# nRF51822_Module_Adapter.net
KiCad netlist of a schematic drawn in EAGLE
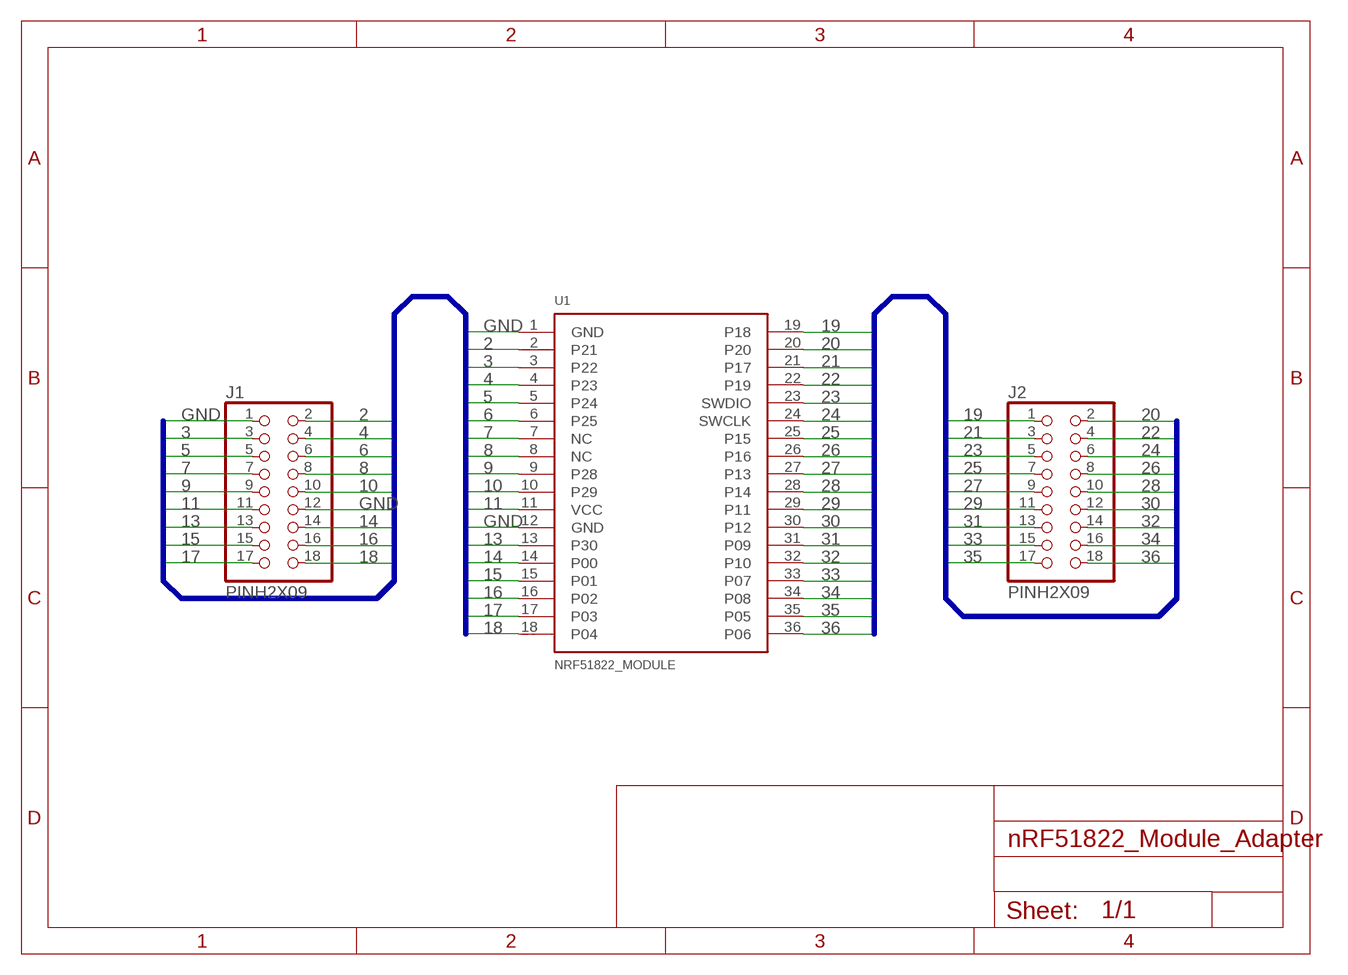
[diagram p0: schematic, sheet 1]

(export (version "E")
  (design (tool "Eeschema 10.0.6"))
  (components
    (comp (ref "J1")
      (value "PINH2X09")
      (footprint "eagle-import:PINH2X09")
      (libsource (lib "eagle-import") (part "PINH2X09"))
    )
    (comp (ref "J2")
      (value "PINH2X09")
      (footprint "eagle-import:PINH2X09")
      (libsource (lib "eagle-import") (part "PINH2X09"))
    )
    (comp (ref "U1")
      (value "NRF51822_MODULE")
      (footprint "eagle-import:NRF51822_MODULE")
      (libsource (lib "eagle-import") (part "NRF51822_MODULE"))
    )
  )
  (nets
    (net (code "1") (name "/2") (class "Default")
      (node (ref "J1") (pin "2") (pinfunction "2_2") (pintype "passive"))
      (node (ref "U1") (pin "2") (pinfunction "P21_2") (pintype "bidirectional"))
    )
    (net (code "2") (name "/3") (class "Default")
      (node (ref "J1") (pin "3") (pinfunction "3_3") (pintype "passive"))
      (node (ref "U1") (pin "3") (pinfunction "P22_3") (pintype "bidirectional"))
    )
    (net (code "3") (name "/4") (class "Default")
      (node (ref "J1") (pin "4") (pinfunction "4_4") (pintype "passive"))
      (node (ref "U1") (pin "4") (pinfunction "P23_4") (pintype "bidirectional"))
    )
    (net (code "4") (name "/5") (class "Default")
      (node (ref "J1") (pin "5") (pinfunction "5_5") (pintype "passive"))
      (node (ref "U1") (pin "5") (pinfunction "P24_5") (pintype "bidirectional"))
    )
    (net (code "5") (name "/6") (class "Default")
      (node (ref "J1") (pin "6") (pinfunction "6_6") (pintype "passive"))
      (node (ref "U1") (pin "6") (pinfunction "P25_6") (pintype "bidirectional"))
    )
    (net (code "6") (name "/7") (class "Default")
      (node (ref "J1") (pin "7") (pinfunction "7_7") (pintype "passive"))
      (node (ref "U1") (pin "7") (pinfunction "NC_7") (pintype "bidirectional"))
    )
    (net (code "7") (name "/8") (class "Default")
      (node (ref "J1") (pin "8") (pinfunction "8_8") (pintype "passive"))
      (node (ref "U1") (pin "8") (pinfunction "NC_8") (pintype "bidirectional"))
    )
    (net (code "8") (name "/9") (class "Default")
      (node (ref "J1") (pin "9") (pinfunction "9_9") (pintype "passive"))
      (node (ref "U1") (pin "9") (pinfunction "P28_9") (pintype "bidirectional"))
    )
    (net (code "9") (name "/10") (class "Default")
      (node (ref "J1") (pin "10") (pinfunction "10_10") (pintype "passive"))
      (node (ref "U1") (pin "10") (pinfunction "P29_10") (pintype "bidirectional"))
    )
    (net (code "10") (name "/11") (class "Default")
      (node (ref "J1") (pin "11") (pinfunction "11_11") (pintype "passive"))
      (node (ref "U1") (pin "11") (pinfunction "VCC_11") (pintype "bidirectional"))
    )
    (net (code "11") (name "/13") (class "Default")
      (node (ref "J1") (pin "13") (pinfunction "13_13") (pintype "passive"))
      (node (ref "U1") (pin "13") (pinfunction "P30_13") (pintype "bidirectional"))
    )
    (net (code "12") (name "/14") (class "Default")
      (node (ref "J1") (pin "14") (pinfunction "14_14") (pintype "passive"))
      (node (ref "U1") (pin "14") (pinfunction "P00_14") (pintype "bidirectional"))
    )
    (net (code "13") (name "/15") (class "Default")
      (node (ref "J1") (pin "15") (pinfunction "15_15") (pintype "passive"))
      (node (ref "U1") (pin "15") (pinfunction "P01_15") (pintype "bidirectional"))
    )
    (net (code "14") (name "/16") (class "Default")
      (node (ref "J1") (pin "16") (pinfunction "16_16") (pintype "passive"))
      (node (ref "U1") (pin "16") (pinfunction "P02_16") (pintype "bidirectional"))
    )
    (net (code "15") (name "/17") (class "Default")
      (node (ref "J1") (pin "17") (pinfunction "17_17") (pintype "passive"))
      (node (ref "U1") (pin "17") (pinfunction "P03_17") (pintype "bidirectional"))
    )
    (net (code "16") (name "/18") (class "Default")
      (node (ref "J1") (pin "18") (pinfunction "18_18") (pintype "passive"))
      (node (ref "U1") (pin "18") (pinfunction "P04_18") (pintype "bidirectional"))
    )
    (net (code "17") (name "/19") (class "Default")
      (node (ref "J2") (pin "1") (pinfunction "1_1") (pintype "passive"))
      (node (ref "U1") (pin "19") (pinfunction "P18_19") (pintype "bidirectional"))
    )
    (net (code "18") (name "/20") (class "Default")
      (node (ref "J2") (pin "2") (pinfunction "2_2") (pintype "passive"))
      (node (ref "U1") (pin "20") (pinfunction "P20_20") (pintype "bidirectional"))
    )
    (net (code "19") (name "/21") (class "Default")
      (node (ref "J2") (pin "3") (pinfunction "3_3") (pintype "passive"))
      (node (ref "U1") (pin "21") (pinfunction "P17_21") (pintype "bidirectional"))
    )
    (net (code "20") (name "/22") (class "Default")
      (node (ref "J2") (pin "4") (pinfunction "4_4") (pintype "passive"))
      (node (ref "U1") (pin "22") (pinfunction "P19_22") (pintype "bidirectional"))
    )
    (net (code "21") (name "/23") (class "Default")
      (node (ref "J2") (pin "5") (pinfunction "5_5") (pintype "passive"))
      (node (ref "U1") (pin "23") (pinfunction "SWDIO_23") (pintype "bidirectional"))
    )
    (net (code "22") (name "/24") (class "Default")
      (node (ref "J2") (pin "6") (pinfunction "6_6") (pintype "passive"))
      (node (ref "U1") (pin "24") (pinfunction "SWCLK_24") (pintype "bidirectional"))
    )
    (net (code "23") (name "/25") (class "Default")
      (node (ref "J2") (pin "7") (pinfunction "7_7") (pintype "passive"))
      (node (ref "U1") (pin "25") (pinfunction "P15_25") (pintype "bidirectional"))
    )
    (net (code "24") (name "/26") (class "Default")
      (node (ref "J2") (pin "8") (pinfunction "8_8") (pintype "passive"))
      (node (ref "U1") (pin "26") (pinfunction "P16_26") (pintype "bidirectional"))
    )
    (net (code "25") (name "/27") (class "Default")
      (node (ref "J2") (pin "9") (pinfunction "9_9") (pintype "passive"))
      (node (ref "U1") (pin "27") (pinfunction "P13_27") (pintype "bidirectional"))
    )
    (net (code "26") (name "/28") (class "Default")
      (node (ref "J2") (pin "10") (pinfunction "10_10") (pintype "passive"))
      (node (ref "U1") (pin "28") (pinfunction "P14_28") (pintype "bidirectional"))
    )
    (net (code "27") (name "/29") (class "Default")
      (node (ref "J2") (pin "11") (pinfunction "11_11") (pintype "passive"))
      (node (ref "U1") (pin "29") (pinfunction "P11_29") (pintype "bidirectional"))
    )
    (net (code "28") (name "/30") (class "Default")
      (node (ref "J2") (pin "12") (pinfunction "12_12") (pintype "passive"))
      (node (ref "U1") (pin "30") (pinfunction "P12_30") (pintype "bidirectional"))
    )
    (net (code "29") (name "/31") (class "Default")
      (node (ref "J2") (pin "13") (pinfunction "13_13") (pintype "passive"))
      (node (ref "U1") (pin "31") (pinfunction "P09_31") (pintype "bidirectional"))
    )
    (net (code "30") (name "/32") (class "Default")
      (node (ref "J2") (pin "14") (pinfunction "14_14") (pintype "passive"))
      (node (ref "U1") (pin "32") (pinfunction "P10_32") (pintype "bidirectional"))
    )
    (net (code "31") (name "/33") (class "Default")
      (node (ref "J2") (pin "15") (pinfunction "15_15") (pintype "passive"))
      (node (ref "U1") (pin "33") (pinfunction "P07_33") (pintype "bidirectional"))
    )
    (net (code "32") (name "/34") (class "Default")
      (node (ref "J2") (pin "16") (pinfunction "16_16") (pintype "passive"))
      (node (ref "U1") (pin "34") (pinfunction "P08_34") (pintype "bidirectional"))
    )
    (net (code "33") (name "/35") (class "Default")
      (node (ref "J2") (pin "17") (pinfunction "17_17") (pintype "passive"))
      (node (ref "U1") (pin "35") (pinfunction "P05_35") (pintype "bidirectional"))
    )
    (net (code "34") (name "/36") (class "Default")
      (node (ref "J2") (pin "18") (pinfunction "18_18") (pintype "passive"))
      (node (ref "U1") (pin "36") (pinfunction "P06_36") (pintype "bidirectional"))
    )
    (net (code "35") (name "/GND") (class "Default")
      (node (ref "J1") (pin "1") (pinfunction "1_1") (pintype "passive"))
      (node (ref "J1") (pin "12") (pinfunction "12_12") (pintype "passive"))
      (node (ref "U1") (pin "1") (pinfunction "GND_1") (pintype "bidirectional"))
      (node (ref "U1") (pin "12") (pinfunction "GND_12") (pintype "bidirectional"))
    )
  )
)
